# reverb.net
KiCad netlist of a schematic drawn in EAGLE
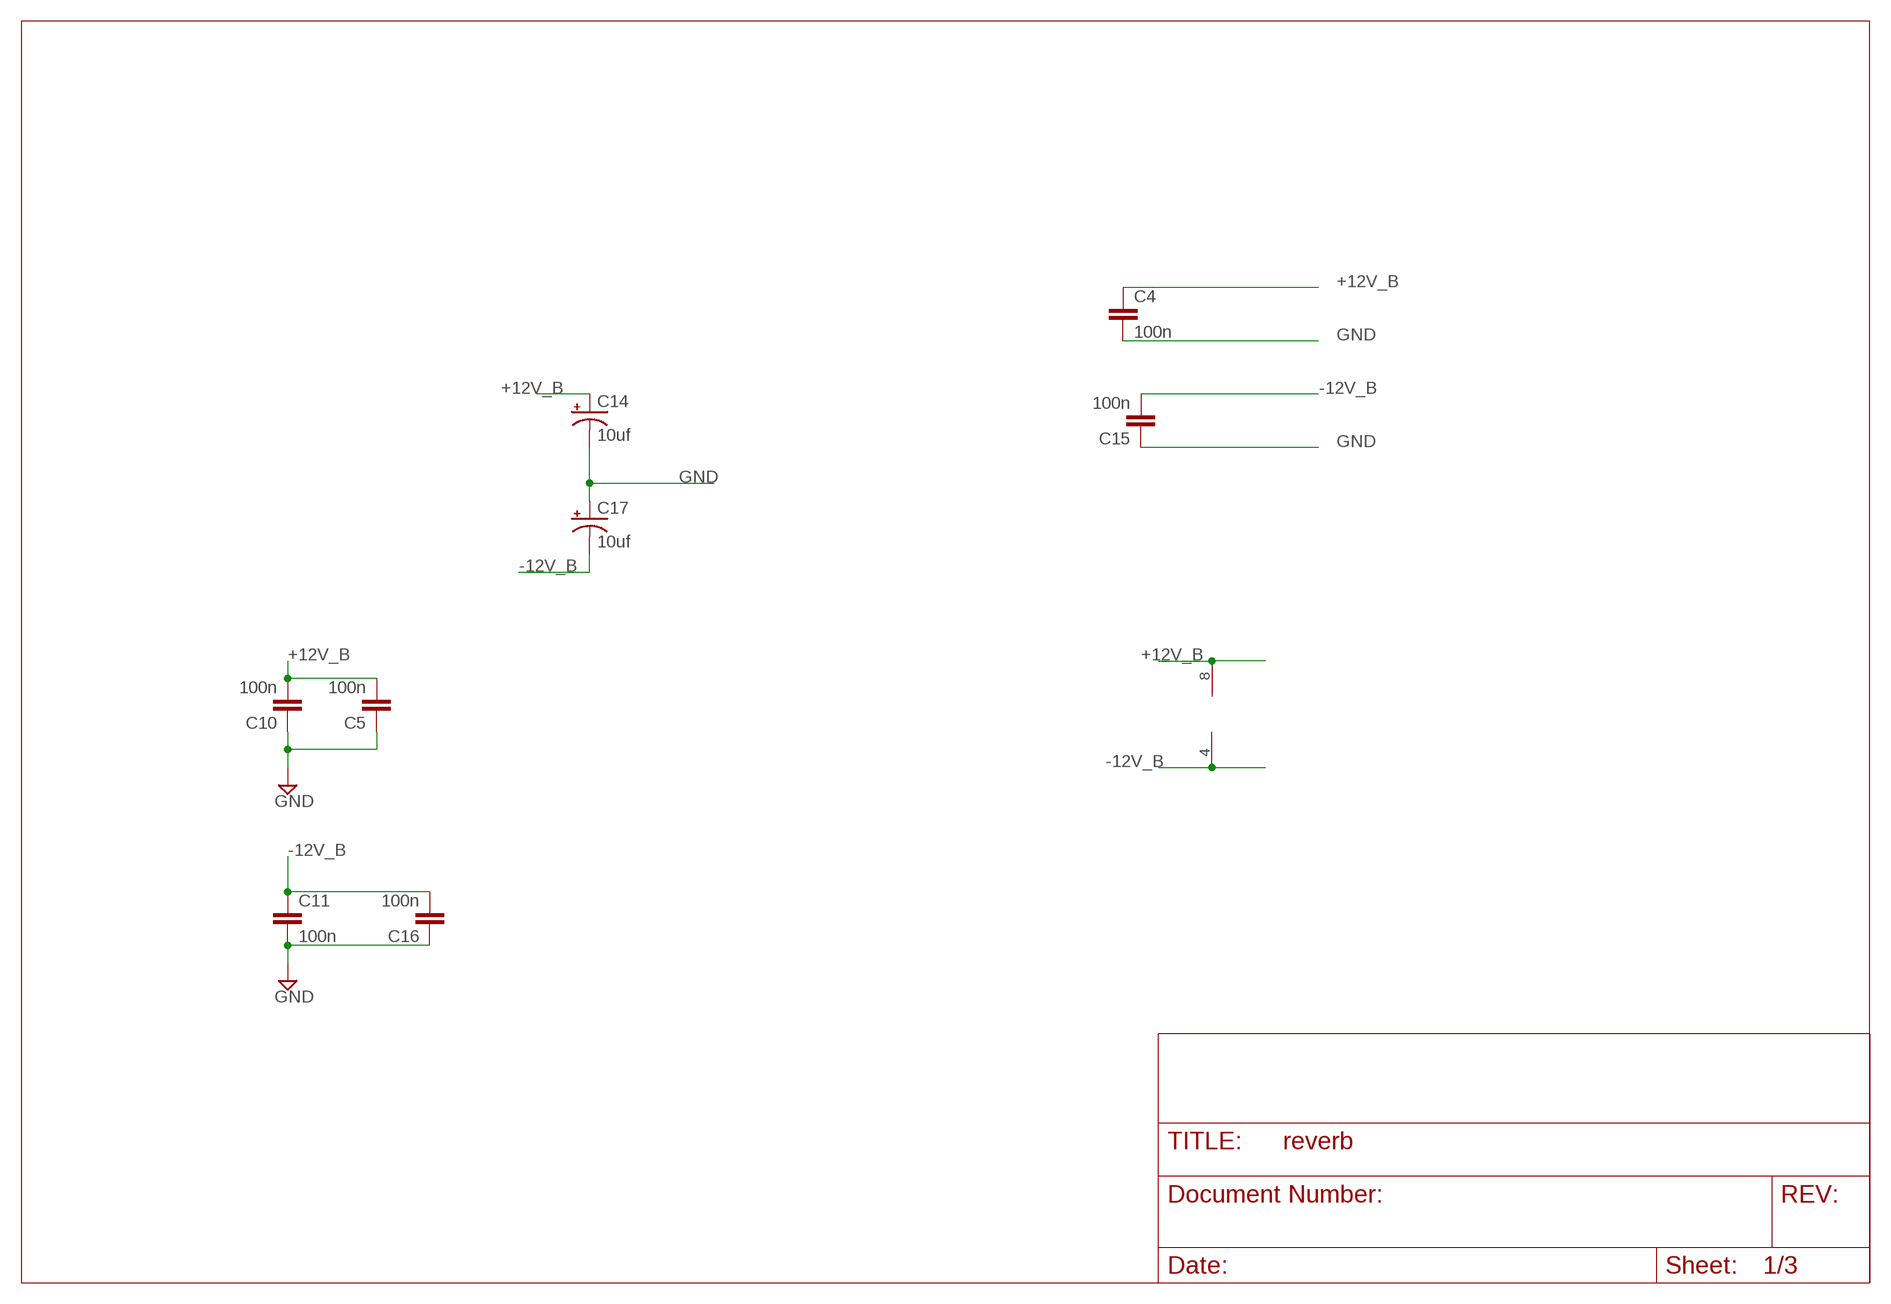
[diagram p0: schematic, sheet 1]
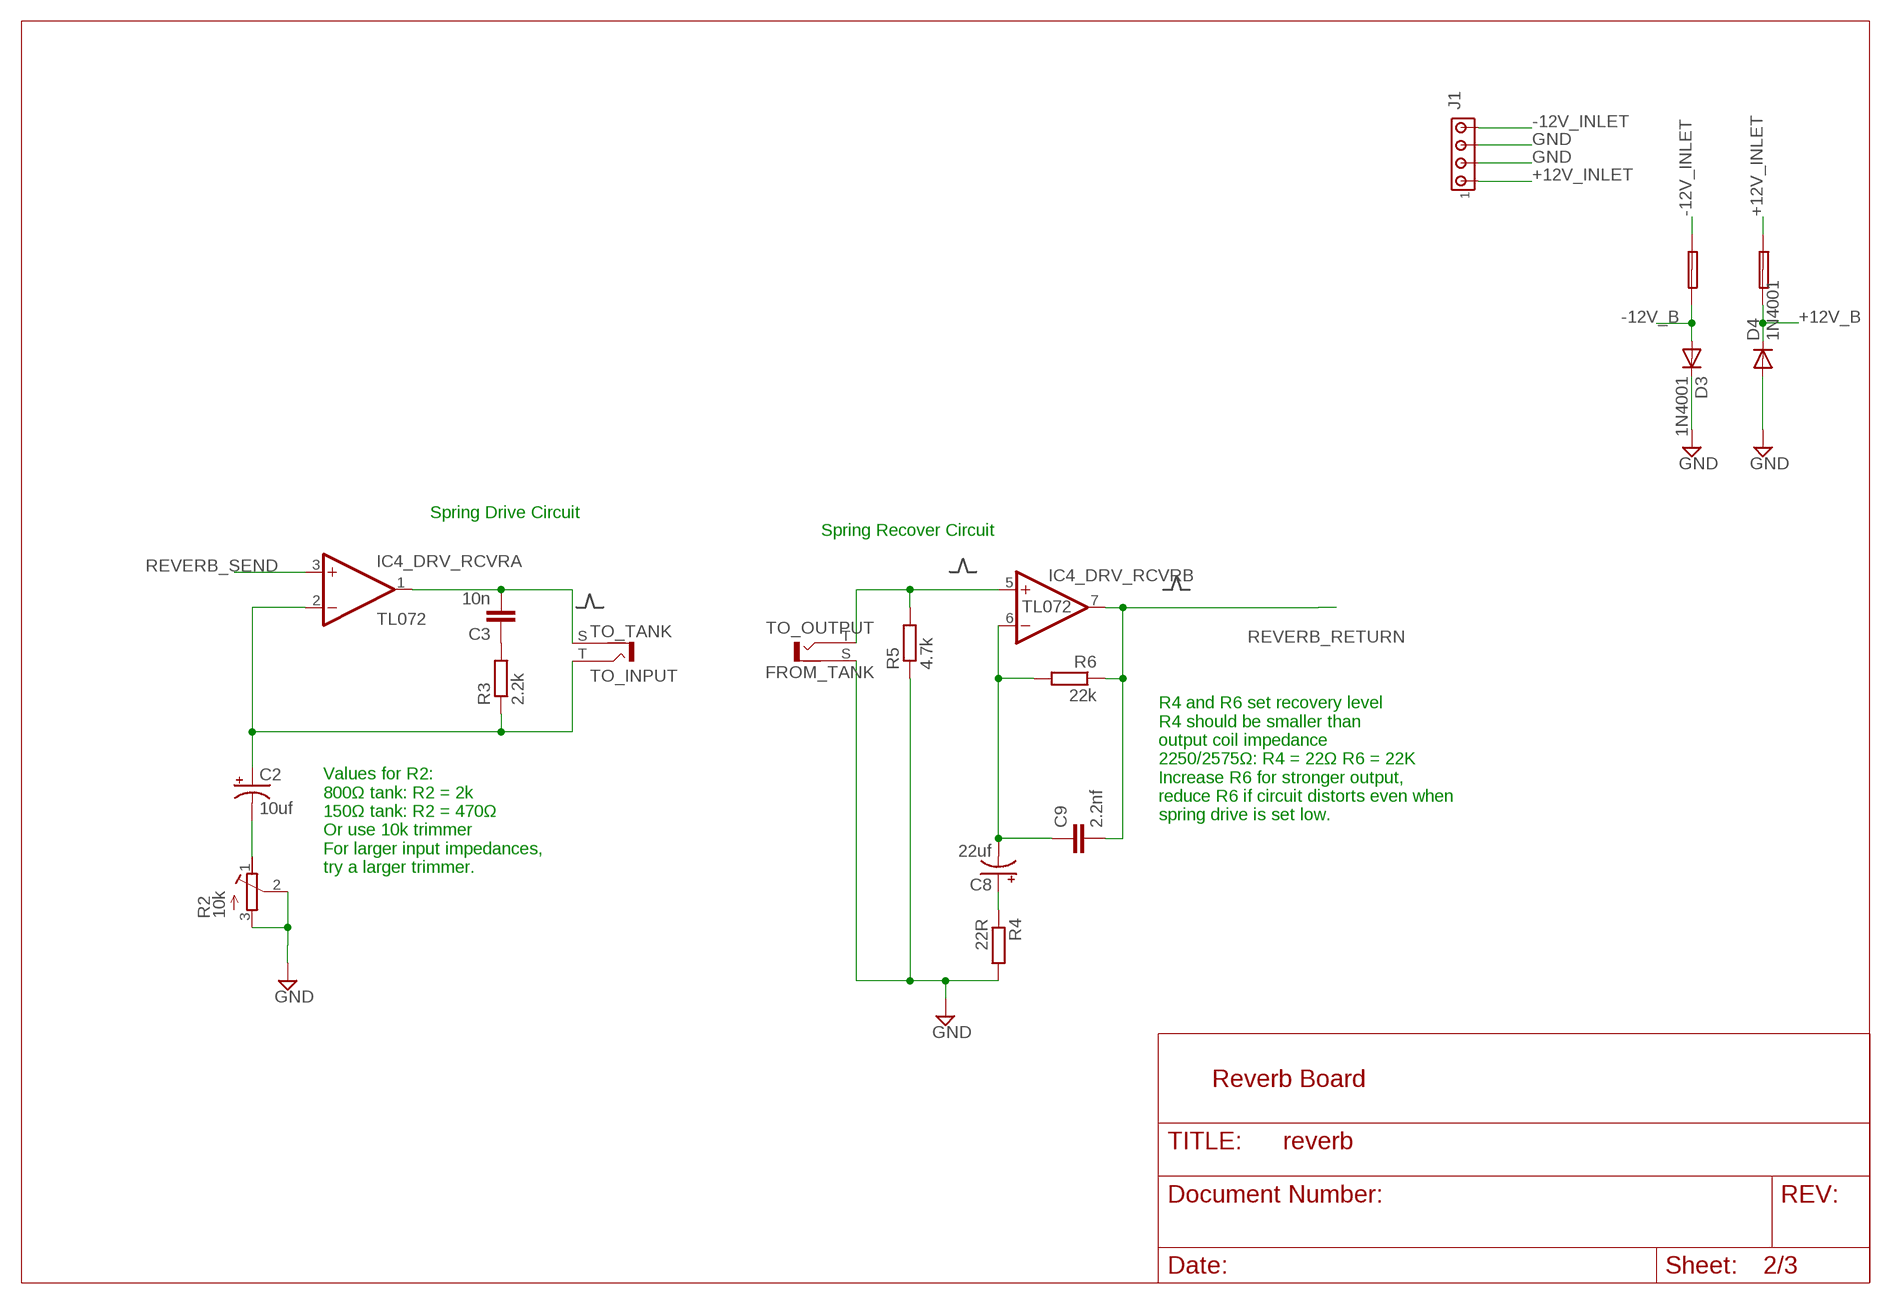
[diagram p1: schematic, sheet 2]
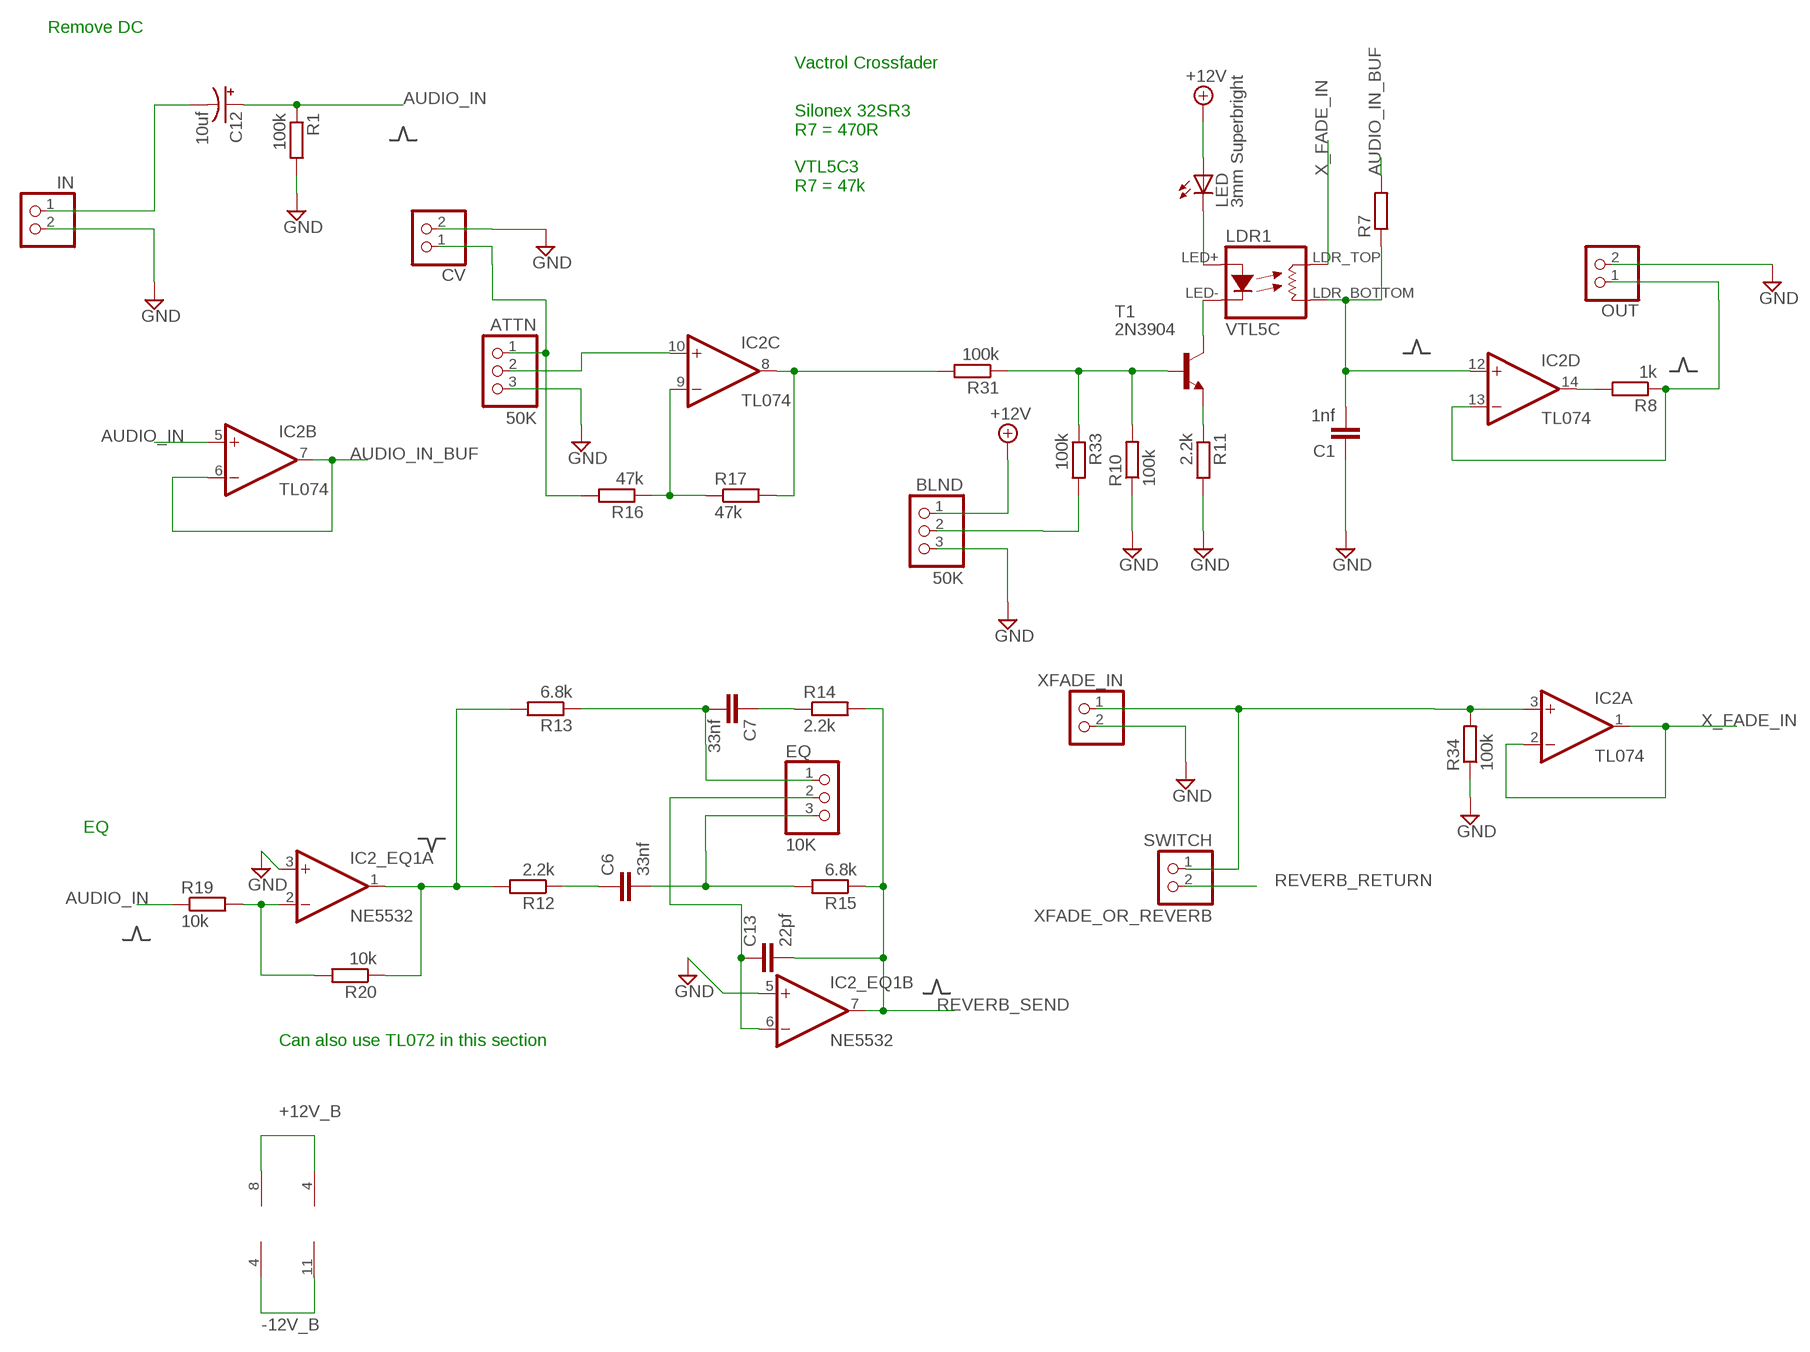
[diagram p2: schematic, sheet 3]

(export (version "E")
  (design (tool "Eeschema 10.0.6"))
  (components
    (comp (ref "0.1A_FUSE")
      (value "FUSE")
      (footprint "eagle-import:C050H075X075")
      (libsource (lib "eagle-import") (part "PTC_FUSEPOLY_FUSE"))
    )
    (comp (ref "0.1A_FUSE_2")
      (value "FUSE")
      (footprint "eagle-import:C050H075X075")
      (libsource (lib "eagle-import") (part "PTC_FUSEPOLY_FUSE"))
    )
    (comp (ref "C2")
      (value "10uf")
      (footprint "eagle-import:CPOL-RADIAL-10UF-25V")
      (libsource (lib "eagle-import") (part "CAP_POLPTH2"))
    )
    (comp (ref "C3")
      (value "10n")
      (footprint "eagle-import:C050-024X044")
      (libsource (lib "eagle-import") (part "C-EU050-024X044"))
    )
    (comp (ref "C8")
      (value "22uf")
      (footprint "eagle-import:CPOL-RADIAL-10UF-25V")
      (libsource (lib "eagle-import") (part "CAP_POLPTH2"))
    )
    (comp (ref "C9")
      (value "2.2nf")
      (footprint "eagle-import:C050-024X044")
      (libsource (lib "eagle-import") (part "C-EU050-024X044"))
    )
    (comp (ref "D3")
      (value "1N4001")
      (footprint "eagle-import:DO41-10")
      (libsource (lib "eagle-import") (part "1N4004"))
    )
    (comp (ref "D4")
      (value "1N4001")
      (footprint "eagle-import:DO41-10")
      (libsource (lib "eagle-import") (part "1N4004"))
    )
    (comp (ref "IC4_DRV_RCVR")
      (value "TL072")
      (footprint "eagle-import:DIL08")
      (libsource (lib "eagle-import") (part "TL072P"))
    )
    (comp (ref "J1")
      (value "MTA04-156")
      (footprint "eagle-import:1X4MTA")
      (libsource (lib "eagle-import") (part "MTA04-156"))
    )
    (comp (ref "R2")
      (value "10k")
      (footprint "eagle-import:RTRIMT93YA")
      (libsource (lib "eagle-import") (part "R-TRIMMT93YA"))
    )
    (comp (ref "R3")
      (value "2.2k")
      (footprint "eagle-import:0207_10")
      (libsource (lib "eagle-import") (part "R-EU_STANDARD_RESISTOR"))
    )
    (comp (ref "R4")
      (value "22R")
      (footprint "eagle-import:0207_10")
      (libsource (lib "eagle-import") (part "R-EU_STANDARD_RESISTOR"))
    )
    (comp (ref "R5")
      (value "4.7k")
      (footprint "eagle-import:0207_10")
      (libsource (lib "eagle-import") (part "R-EU_STANDARD_RESISTOR"))
    )
    (comp (ref "R6")
      (value "22k")
      (footprint "eagle-import:0207_10")
      (libsource (lib "eagle-import") (part "R-EU_STANDARD_RESISTOR"))
    )
    (comp (ref "TO_INPUT")
      (value "TO_TANK")
      (footprint "eagle-import:BTOR1")
      (fields (field (name "MPN") "BTOR 1"))
      (libsource (lib "eagle-import") (part "BTOR1"))
    )
    (comp (ref "TO_OUTPUT")
      (value "FROM_TANK")
      (footprint "eagle-import:BTOR1")
      (fields (field (name "MPN") "BTOR 1"))
      (libsource (lib "eagle-import") (part "BTOR1"))
    )
    (comp (ref "C4")
      (value "100n")
      (footprint "eagle-import:C050-024X044")
      (libsource (lib "eagle-import") (part "C-EU050-024X044"))
    )
    (comp (ref "C5")
      (value "100n")
      (footprint "eagle-import:C050-024X044")
      (libsource (lib "eagle-import") (part "C-EU050-024X044"))
    )
    (comp (ref "C10")
      (value "100n")
      (footprint "eagle-import:C050-024X044")
      (libsource (lib "eagle-import") (part "C-EU050-024X044"))
    )
    (comp (ref "C11")
      (value "100n")
      (footprint "eagle-import:C050-024X044")
      (libsource (lib "eagle-import") (part "C-EU050-024X044"))
    )
    (comp (ref "C14")
      (value "10uf")
      (footprint "eagle-import:CPOL-RADIAL-10UF-25V")
      (libsource (lib "eagle-import") (part "CAP_POLPTH2"))
    )
    (comp (ref "C15")
      (value "100n")
      (footprint "eagle-import:C050-024X044")
      (libsource (lib "eagle-import") (part "C-EU050-024X044"))
    )
    (comp (ref "C16")
      (value "100n")
      (footprint "eagle-import:C050-024X044")
      (libsource (lib "eagle-import") (part "C-EU050-024X044"))
    )
    (comp (ref "C17")
      (value "10uf")
      (footprint "eagle-import:CPOL-RADIAL-10UF-25V")
      (libsource (lib "eagle-import") (part "CAP_POLPTH2"))
    )
    (comp (ref "ATTN")
      (value "50K")
      (footprint "eagle-import:1X03")
      (libsource (lib "eagle-import") (part "PINHD-1X3"))
    )
    (comp (ref "BLND")
      (value "50K")
      (footprint "eagle-import:1X03")
      (libsource (lib "eagle-import") (part "PINHD-1X3"))
    )
    (comp (ref "C1")
      (value "1nf")
      (footprint "eagle-import:C050-024X044")
      (libsource (lib "eagle-import") (part "C-EU050-024X044"))
    )
    (comp (ref "C6")
      (value "33nf")
      (footprint "eagle-import:C050-024X044")
      (libsource (lib "eagle-import") (part "C-EU050-024X044"))
    )
    (comp (ref "C7")
      (value "33nf")
      (footprint "eagle-import:C050-024X044")
      (libsource (lib "eagle-import") (part "C-EU050-024X044"))
    )
    (comp (ref "C12")
      (value "10uf")
      (footprint "eagle-import:050_020")
      (libsource (lib "eagle-import") (part "050"))
    )
    (comp (ref "C13")
      (value "22pf")
      (footprint "eagle-import:050X030_025")
      (libsource (lib "eagle-import") (part "050X030_0251"))
    )
    (comp (ref "CV")
      (value "PINHD-1X2")
      (footprint "eagle-import:1X02")
      (libsource (lib "eagle-import") (part "PINHD-1X2"))
    )
    (comp (ref "EQ")
      (value "10K")
      (footprint "eagle-import:1X03")
      (libsource (lib "eagle-import") (part "PINHD-1X3"))
    )
    (comp (ref "IC2")
      (value "TL074")
      (footprint "eagle-import:DIL14")
      (libsource (lib "eagle-import") (part "TL074P"))
    )
    (comp (ref "IC2_EQ1")
      (value "NE5532")
      (footprint "eagle-import:DIL08")
      (libsource (lib "eagle-import") (part "TL072P"))
    )
    (comp (ref "IN")
      (value "PINHD-1X2")
      (footprint "eagle-import:1X02")
      (libsource (lib "eagle-import") (part "PINHD-1X2"))
    )
    (comp (ref "LDR1")
      (value "VTL5C")
      (footprint "eagle-import:VACTROL_COMPACT")
      (libsource (lib "eagle-import") (part "VACTROL_COMPACT"))
    )
    (comp (ref "LED")
      (value "3mm Superbright")
      (footprint "eagle-import:LED3MM")
      (libsource (lib "eagle-import") (part "LED3MM"))
    )
    (comp (ref "OUT")
      (value "PINHD-1X2")
      (footprint "eagle-import:1X02")
      (libsource (lib "eagle-import") (part "PINHD-1X2"))
    )
    (comp (ref "R1")
      (value "100k")
      (footprint "eagle-import:VERT-RESISTOR")
      (libsource (lib "eagle-import") (part "VERT-RESIST1"))
    )
    (comp (ref "R7")
      (value "R-EU_STANDARD_RESISTOR")
      (footprint "eagle-import:0207_10")
      (libsource (lib "eagle-import") (part "R-EU_STANDARD_RESISTOR"))
    )
    (comp (ref "R8")
      (value "1k")
      (footprint "eagle-import:0207_10")
      (libsource (lib "eagle-import") (part "R-EU_STANDARD_RESISTOR"))
    )
    (comp (ref "R10")
      (value "100k")
      (footprint "eagle-import:0207_10")
      (libsource (lib "eagle-import") (part "R-EU_STANDARD_RESISTOR"))
    )
    (comp (ref "R11")
      (value "2.2k")
      (footprint "eagle-import:0207_10")
      (libsource (lib "eagle-import") (part "R-EU_STANDARD_RESISTOR"))
    )
    (comp (ref "R12")
      (value "2.2k")
      (footprint "eagle-import:0207_10")
      (libsource (lib "eagle-import") (part "R-EU_STANDARD_RESISTOR"))
    )
    (comp (ref "R13")
      (value "6.8k")
      (footprint "eagle-import:0207_10")
      (libsource (lib "eagle-import") (part "R-EU_STANDARD_RESISTOR"))
    )
    (comp (ref "R14")
      (value "2.2k")
      (footprint "eagle-import:0207_10")
      (libsource (lib "eagle-import") (part "R-EU_STANDARD_RESISTOR"))
    )
    (comp (ref "R15")
      (value "6.8k")
      (footprint "eagle-import:0207_10")
      (libsource (lib "eagle-import") (part "R-EU_STANDARD_RESISTOR"))
    )
    (comp (ref "R16")
      (value "47k")
      (footprint "eagle-import:VERT-RESISTOR")
      (libsource (lib "eagle-import") (part "VERT-RESIST1"))
    )
    (comp (ref "R17")
      (value "47k")
      (footprint "eagle-import:VERT-RESISTOR")
      (libsource (lib "eagle-import") (part "VERT-RESIST1"))
    )
    (comp (ref "R19")
      (value "10k")
      (footprint "eagle-import:VERT-RESISTOR")
      (libsource (lib "eagle-import") (part "VERT-RESIST1"))
    )
    (comp (ref "R20")
      (value "10k")
      (footprint "eagle-import:0207_10")
      (libsource (lib "eagle-import") (part "R-EU_STANDARD_RESISTOR"))
    )
    (comp (ref "R31")
      (value "100k")
      (footprint "eagle-import:0207_10")
      (libsource (lib "eagle-import") (part "R-EU_STANDARD_RESISTOR"))
    )
    (comp (ref "R33")
      (value "100k")
      (footprint "eagle-import:0207_10")
      (libsource (lib "eagle-import") (part "R-EU_STANDARD_RESISTOR"))
    )
    (comp (ref "R34")
      (value "100k")
      (footprint "eagle-import:0207_10")
      (libsource (lib "eagle-import") (part "R-EU_STANDARD_RESISTOR"))
    )
    (comp (ref "SWITCH")
      (value "XFADE_OR_REVERB")
      (footprint "eagle-import:1X02")
      (libsource (lib "eagle-import") (part "PINHD-1X2"))
    )
    (comp (ref "T1")
      (value "2N3904")
      (footprint "eagle-import:TO92")
      (libsource (lib "eagle-import") (part "2N3904"))
    )
    (comp (ref "XFADE_IN")
      (value "PINHD-1X2")
      (footprint "eagle-import:1X02")
      (libsource (lib "eagle-import") (part "PINHD-1X2"))
    )
  )
  (nets
    (net (code "1") (name "+12V") (class "Default")
      (node (ref "BLND") (pin "1") (pinfunction "1_1") (pintype "passive"))
      (node (ref "LED") (pin "A") (pinfunction "A_A") (pintype "passive"))
    )
    (net (code "2") (name "+12V_B") (class "Default")
      (node (ref "0.1A_FUSE_2") (pin "1") (pinfunction "P$1_1") (pintype "bidirectional"))
      (node (ref "C10") (pin "2") (pinfunction "2_2") (pintype "passive"))
      (node (ref "C14") (pin "1") (pinfunction "+_1") (pintype "passive"))
      (node (ref "C4") (pin "1") (pinfunction "1_1") (pintype "passive"))
      (node (ref "C5") (pin "2") (pinfunction "2_2") (pintype "passive"))
      (node (ref "D4") (pin "C") (pinfunction "C_C") (pintype "passive"))
      (node (ref "IC2") (pin "4") (pinfunction "V+_4") (pintype "power_in"))
      (node (ref "IC2_EQ1") (pin "8") (pinfunction "V+_8") (pintype "power_in"))
      (node (ref "IC4_DRV_RCVR") (pin "8") (pinfunction "V+_8") (pintype "power_in"))
    )
    (net (code "3") (name "+12V_INLET") (class "Default")
      (node (ref "0.1A_FUSE_2") (pin "2") (pinfunction "P$2_2") (pintype "bidirectional"))
      (node (ref "J1") (pin "1") (pinfunction "1_1") (pintype "passive"))
    )
    (net (code "4") (name "-12V_B") (class "Default")
      (node (ref "0.1A_FUSE") (pin "1") (pinfunction "P$1_1") (pintype "bidirectional"))
      (node (ref "C11") (pin "1") (pinfunction "1_1") (pintype "passive"))
      (node (ref "C15") (pin "2") (pinfunction "2_2") (pintype "passive"))
      (node (ref "C16") (pin "2") (pinfunction "2_2") (pintype "passive"))
      (node (ref "C17") (pin "2") (pinfunction "-_2") (pintype "passive"))
      (node (ref "D3") (pin "A") (pinfunction "A_A") (pintype "passive"))
      (node (ref "IC2") (pin "11") (pinfunction "V-_11") (pintype "power_in"))
      (node (ref "IC2_EQ1") (pin "4") (pinfunction "V-_4") (pintype "power_in"))
      (node (ref "IC4_DRV_RCVR") (pin "4") (pinfunction "V-_4") (pintype "power_in"))
    )
    (net (code "5") (name "-12V_INLET") (class "Default")
      (node (ref "0.1A_FUSE") (pin "2") (pinfunction "P$2_2") (pintype "bidirectional"))
      (node (ref "J1") (pin "4") (pinfunction "4_4") (pintype "passive"))
    )
    (net (code "6") (name "AUDIO_IN") (class "Default")
      (node (ref "C12") (pin "+") (pinfunction "+_+") (pintype "passive"))
      (node (ref "IC2") (pin "5") (pinfunction "+IN_5") (pintype "input"))
      (node (ref "R1") (pin "1") (pinfunction "1_1") (pintype "passive"))
      (node (ref "R19") (pin "1") (pinfunction "1_1") (pintype "passive"))
    )
    (net (code "7") (name "AUDIO_IN_BUF") (class "Default")
      (node (ref "IC2") (pin "6") (pinfunction "-IN_6") (pintype "input"))
      (node (ref "IC2") (pin "7") (pinfunction "OUT_7") (pintype "output"))
      (node (ref "R7") (pin "2") (pinfunction "2_2") (pintype "passive"))
    )
    (net (code "8") (name "GND") (class "Default")
      (node (ref "ATTN") (pin "3") (pinfunction "3_3") (pintype "passive"))
      (node (ref "BLND") (pin "3") (pinfunction "3_3") (pintype "passive"))
      (node (ref "C1") (pin "1") (pinfunction "1_1") (pintype "passive"))
      (node (ref "C10") (pin "1") (pinfunction "1_1") (pintype "passive"))
      (node (ref "C11") (pin "2") (pinfunction "2_2") (pintype "passive"))
      (node (ref "C14") (pin "2") (pinfunction "-_2") (pintype "passive"))
      (node (ref "C15") (pin "1") (pinfunction "1_1") (pintype "passive"))
      (node (ref "C16") (pin "1") (pinfunction "1_1") (pintype "passive"))
      (node (ref "C17") (pin "1") (pinfunction "+_1") (pintype "passive"))
      (node (ref "C4") (pin "2") (pinfunction "2_2") (pintype "passive"))
      (node (ref "C5") (pin "1") (pinfunction "1_1") (pintype "passive"))
      (node (ref "CV") (pin "2") (pinfunction "2_2") (pintype "passive"))
      (node (ref "D3") (pin "C") (pinfunction "C_C") (pintype "passive"))
      (node (ref "D4") (pin "A") (pinfunction "A_A") (pintype "passive"))
      (node (ref "IC2_EQ1") (pin "3") (pinfunction "+IN_3") (pintype "input"))
      (node (ref "IC2_EQ1") (pin "5") (pinfunction "+IN_5") (pintype "input"))
      (node (ref "IN") (pin "2") (pinfunction "2_2") (pintype "passive"))
      (node (ref "J1") (pin "2") (pinfunction "2_2") (pintype "passive"))
      (node (ref "J1") (pin "3") (pinfunction "3_3") (pintype "passive"))
      (node (ref "OUT") (pin "2") (pinfunction "2_2") (pintype "passive"))
      (node (ref "R1") (pin "2") (pinfunction "2_2") (pintype "passive"))
      (node (ref "R10") (pin "1") (pinfunction "1_1") (pintype "passive"))
      (node (ref "R11") (pin "2") (pinfunction "2_2") (pintype "passive"))
      (node (ref "R2") (pin "2") (pinfunction "S_2") (pintype "passive"))
      (node (ref "R2") (pin "3") (pinfunction "E_3") (pintype "passive"))
      (node (ref "R34") (pin "1") (pinfunction "1_1") (pintype "passive"))
      (node (ref "R4") (pin "2") (pinfunction "2_2") (pintype "passive"))
      (node (ref "R5") (pin "1") (pinfunction "1_1") (pintype "passive"))
      (node (ref "TO_OUTPUT") (pin "S") (pinfunction "2_S") (pintype "passive"))
      (node (ref "XFADE_IN") (pin "2") (pinfunction "2_2") (pintype "passive"))
    )
    (net (code "9") (name "Net-(ATTN-Pad1)") (class "Default")
      (node (ref "ATTN") (pin "1") (pinfunction "1_1") (pintype "passive"))
      (node (ref "CV") (pin "1") (pinfunction "1_1") (pintype "passive"))
      (node (ref "R16") (pin "2") (pinfunction "2_2") (pintype "passive"))
    )
    (net (code "10") (name "Net-(BLND-Pad2)") (class "Default")
      (node (ref "BLND") (pin "2") (pinfunction "2_2") (pintype "passive"))
      (node (ref "R33") (pin "2") (pinfunction "2_2") (pintype "passive"))
    )
    (net (code "11") (name "Net-(C2-+)") (class "Default")
      (node (ref "C2") (pin "1") (pinfunction "+_1") (pintype "passive"))
      (node (ref "IC4_DRV_RCVR") (pin "2") (pinfunction "-IN_2") (pintype "input"))
      (node (ref "R3") (pin "1") (pinfunction "1_1") (pintype "passive"))
      (node (ref "TO_INPUT") (pin "T") (pinfunction "1_T") (pintype "passive"))
    )
    (net (code "12") (name "Net-(C2--)") (class "Default")
      (node (ref "C2") (pin "2") (pinfunction "-_2") (pintype "passive"))
      (node (ref "R2") (pin "1") (pinfunction "A_1") (pintype "passive"))
    )
    (net (code "13") (name "Net-(C3-Pad1)") (class "Default")
      (node (ref "C3") (pin "1") (pinfunction "1_1") (pintype "passive"))
      (node (ref "R3") (pin "2") (pinfunction "2_2") (pintype "passive"))
    )
    (net (code "14") (name "Net-(C6-Pad1)") (class "Default")
      (node (ref "C6") (pin "1") (pinfunction "1_1") (pintype "passive"))
      (node (ref "R12") (pin "1") (pinfunction "1_1") (pintype "passive"))
    )
    (net (code "15") (name "Net-(C6-Pad2)") (class "Default")
      (node (ref "C6") (pin "2") (pinfunction "2_2") (pintype "passive"))
      (node (ref "EQ") (pin "3") (pinfunction "3_3") (pintype "passive"))
      (node (ref "R15") (pin "2") (pinfunction "2_2") (pintype "passive"))
    )
    (net (code "16") (name "Net-(C7-Pad1)") (class "Default")
      (node (ref "C7") (pin "1") (pinfunction "1_1") (pintype "passive"))
      (node (ref "R14") (pin "1") (pinfunction "1_1") (pintype "passive"))
    )
    (net (code "17") (name "Net-(C7-Pad2)") (class "Default")
      (node (ref "C7") (pin "2") (pinfunction "2_2") (pintype "passive"))
      (node (ref "EQ") (pin "1") (pinfunction "1_1") (pintype "passive"))
      (node (ref "R13") (pin "1") (pinfunction "1_1") (pintype "passive"))
    )
    (net (code "18") (name "Net-(C8-+)") (class "Default")
      (node (ref "C8") (pin "1") (pinfunction "+_1") (pintype "passive"))
      (node (ref "R4") (pin "1") (pinfunction "1_1") (pintype "passive"))
    )
    (net (code "19") (name "Net-(C8--)") (class "Default")
      (node (ref "C8") (pin "2") (pinfunction "-_2") (pintype "passive"))
      (node (ref "C9") (pin "1") (pinfunction "1_1") (pintype "passive"))
      (node (ref "IC4_DRV_RCVR") (pin "6") (pinfunction "-IN_6") (pintype "input"))
      (node (ref "R6") (pin "2") (pinfunction "2_2") (pintype "passive"))
    )
    (net (code "20") (name "Net-(C12-Pad-)") (class "Default")
      (node (ref "C12") (pin "-") (pinfunction "-_-") (pintype "passive"))
      (node (ref "IN") (pin "1") (pinfunction "1_1") (pintype "passive"))
    )
    (net (code "21") (name "Net-(IC2A-+IN)") (class "Default")
      (node (ref "IC2") (pin "3") (pinfunction "+IN_3") (pintype "input"))
      (node (ref "R34") (pin "2") (pinfunction "2_2") (pintype "passive"))
      (node (ref "SWITCH") (pin "1") (pinfunction "1_1") (pintype "passive"))
      (node (ref "XFADE_IN") (pin "1") (pinfunction "1_1") (pintype "passive"))
    )
    (net (code "22") (name "Net-(IC2C-+IN)") (class "Default")
      (node (ref "ATTN") (pin "2") (pinfunction "2_2") (pintype "passive"))
      (node (ref "IC2") (pin "10") (pinfunction "+IN_10") (pintype "input"))
    )
    (net (code "23") (name "Net-(IC2C--IN)") (class "Default")
      (node (ref "IC2") (pin "9") (pinfunction "-IN_9") (pintype "input"))
      (node (ref "R16") (pin "1") (pinfunction "1_1") (pintype "passive"))
      (node (ref "R17") (pin "1") (pinfunction "1_1") (pintype "passive"))
    )
    (net (code "24") (name "Net-(IC2C-OUT)") (class "Default")
      (node (ref "IC2") (pin "8") (pinfunction "OUT_8") (pintype "output"))
      (node (ref "R17") (pin "2") (pinfunction "2_2") (pintype "passive"))
      (node (ref "R31") (pin "2") (pinfunction "2_2") (pintype "passive"))
    )
    (net (code "25") (name "Net-(IC2D-+IN)") (class "Default")
      (node (ref "C1") (pin "2") (pinfunction "2_2") (pintype "passive"))
      (node (ref "IC2") (pin "12") (pinfunction "+IN_12") (pintype "input"))
      (node (ref "LDR1") (pin "LDR_BOTTOM") (pinfunction "RES2_LDR_BOTTOM") (pintype "passive"))
      (node (ref "R7") (pin "1") (pinfunction "1_1") (pintype "passive"))
    )
    (net (code "26") (name "Net-(IC2D--IN)") (class "Default")
      (node (ref "IC2") (pin "13") (pinfunction "-IN_13") (pintype "input"))
      (node (ref "OUT") (pin "1") (pinfunction "1_1") (pintype "passive"))
      (node (ref "R8") (pin "1") (pinfunction "1_1") (pintype "passive"))
    )
    (net (code "27") (name "Net-(IC2D-OUT)") (class "Default")
      (node (ref "IC2") (pin "14") (pinfunction "OUT_14") (pintype "output"))
      (node (ref "R8") (pin "2") (pinfunction "2_2") (pintype "passive"))
    )
    (net (code "28") (name "Net-(IC2_EQ1A--IN)") (class "Default")
      (node (ref "IC2_EQ1") (pin "2") (pinfunction "-IN_2") (pintype "input"))
      (node (ref "R19") (pin "2") (pinfunction "2_2") (pintype "passive"))
      (node (ref "R20") (pin "2") (pinfunction "2_2") (pintype "passive"))
    )
    (net (code "29") (name "Net-(IC2_EQ1A-OUT)") (class "Default")
      (node (ref "IC2_EQ1") (pin "1") (pinfunction "OUT_1") (pintype "output"))
      (node (ref "R12") (pin "2") (pinfunction "2_2") (pintype "passive"))
      (node (ref "R13") (pin "2") (pinfunction "2_2") (pintype "passive"))
      (node (ref "R20") (pin "1") (pinfunction "1_1") (pintype "passive"))
    )
    (net (code "30") (name "Net-(IC2_EQ1B--IN)") (class "Default")
      (node (ref "C13") (pin "1") (pinfunction "1_1") (pintype "passive"))
      (node (ref "EQ") (pin "2") (pinfunction "2_2") (pintype "passive"))
      (node (ref "IC2_EQ1") (pin "6") (pinfunction "-IN_6") (pintype "input"))
    )
    (net (code "31") (name "Net-(IC4_DRV_RCVRA-OUT)") (class "Default")
      (node (ref "C3") (pin "2") (pinfunction "2_2") (pintype "passive"))
      (node (ref "IC4_DRV_RCVR") (pin "1") (pinfunction "OUT_1") (pintype "output"))
      (node (ref "TO_INPUT") (pin "S") (pinfunction "2_S") (pintype "passive"))
    )
    (net (code "32") (name "Net-(IC4_DRV_RCVRB-+IN)") (class "Default")
      (node (ref "IC4_DRV_RCVR") (pin "5") (pinfunction "+IN_5") (pintype "input"))
      (node (ref "R5") (pin "2") (pinfunction "2_2") (pintype "passive"))
      (node (ref "TO_OUTPUT") (pin "T") (pinfunction "1_T") (pintype "passive"))
    )
    (net (code "33") (name "Net-(LED-C)") (class "Default")
      (node (ref "LDR1") (pin "LED+") (pinfunction "LED+_LED+") (pintype "passive"))
      (node (ref "LED") (pin "K") (pinfunction "C_K") (pintype "passive"))
    )
    (net (code "34") (name "Net-(T1-B)") (class "Default")
      (node (ref "R10") (pin "2") (pinfunction "2_2") (pintype "passive"))
      (node (ref "R31") (pin "1") (pinfunction "1_1") (pintype "passive"))
      (node (ref "R33") (pin "1") (pinfunction "1_1") (pintype "passive"))
      (node (ref "T1") (pin "2") (pinfunction "B_2") (pintype "passive"))
    )
    (net (code "35") (name "Net-(T1-C)") (class "Default")
      (node (ref "LDR1") (pin "LED-") (pinfunction "LED-_LED-") (pintype "passive"))
      (node (ref "T1") (pin "1") (pinfunction "C_1") (pintype "passive"))
    )
    (net (code "36") (name "Net-(T1-E)") (class "Default")
      (node (ref "R11") (pin "1") (pinfunction "1_1") (pintype "passive"))
      (node (ref "T1") (pin "3") (pinfunction "E_3") (pintype "passive"))
    )
    (net (code "37") (name "REVERB_RETURN") (class "Default")
      (node (ref "C9") (pin "2") (pinfunction "2_2") (pintype "passive"))
      (node (ref "IC4_DRV_RCVR") (pin "7") (pinfunction "OUT_7") (pintype "output"))
      (node (ref "R6") (pin "1") (pinfunction "1_1") (pintype "passive"))
      (node (ref "SWITCH") (pin "2") (pinfunction "2_2") (pintype "passive"))
    )
    (net (code "38") (name "REVERB_SEND") (class "Default")
      (node (ref "C13") (pin "2") (pinfunction "2_2") (pintype "passive"))
      (node (ref "IC2_EQ1") (pin "7") (pinfunction "OUT_7") (pintype "output"))
      (node (ref "IC4_DRV_RCVR") (pin "3") (pinfunction "+IN_3") (pintype "input"))
      (node (ref "R14") (pin "2") (pinfunction "2_2") (pintype "passive"))
      (node (ref "R15") (pin "1") (pinfunction "1_1") (pintype "passive"))
    )
    (net (code "39") (name "X_FADE_IN") (class "Default")
      (node (ref "IC2") (pin "1") (pinfunction "OUT_1") (pintype "output"))
      (node (ref "IC2") (pin "2") (pinfunction "-IN_2") (pintype "input"))
      (node (ref "LDR1") (pin "LDR_TOP") (pinfunction "RES1_LDR_TOP") (pintype "passive"))
    )
    (net (code "40") (name "unconnected-(TO_INPUT-2-PadS@1)") (class "Default")
      (node (ref "TO_INPUT") (pin "S@1") (pinfunction "2_S@1") (pintype "passive"))
    )
    (net (code "41") (name "unconnected-(TO_INPUT-2-PadS@2)") (class "Default")
      (node (ref "TO_INPUT") (pin "S@2") (pinfunction "2_S@2") (pintype "passive"))
    )
    (net (code "42") (name "unconnected-(TO_INPUT-2-PadS@3)") (class "Default")
      (node (ref "TO_INPUT") (pin "S@3") (pinfunction "2_S@3") (pintype "passive"))
    )
    (net (code "43") (name "unconnected-(TO_OUTPUT-2-PadS@1)") (class "Default")
      (node (ref "TO_OUTPUT") (pin "S@1") (pinfunction "2_S@1") (pintype "passive"))
    )
    (net (code "44") (name "unconnected-(TO_OUTPUT-2-PadS@2)") (class "Default")
      (node (ref "TO_OUTPUT") (pin "S@2") (pinfunction "2_S@2") (pintype "passive"))
    )
    (net (code "45") (name "unconnected-(TO_OUTPUT-2-PadS@3)") (class "Default")
      (node (ref "TO_OUTPUT") (pin "S@3") (pinfunction "2_S@3") (pintype "passive"))
    )
  )
)
